# DownStream.net
KiCad netlist of a schematic drawn in Altium Designer
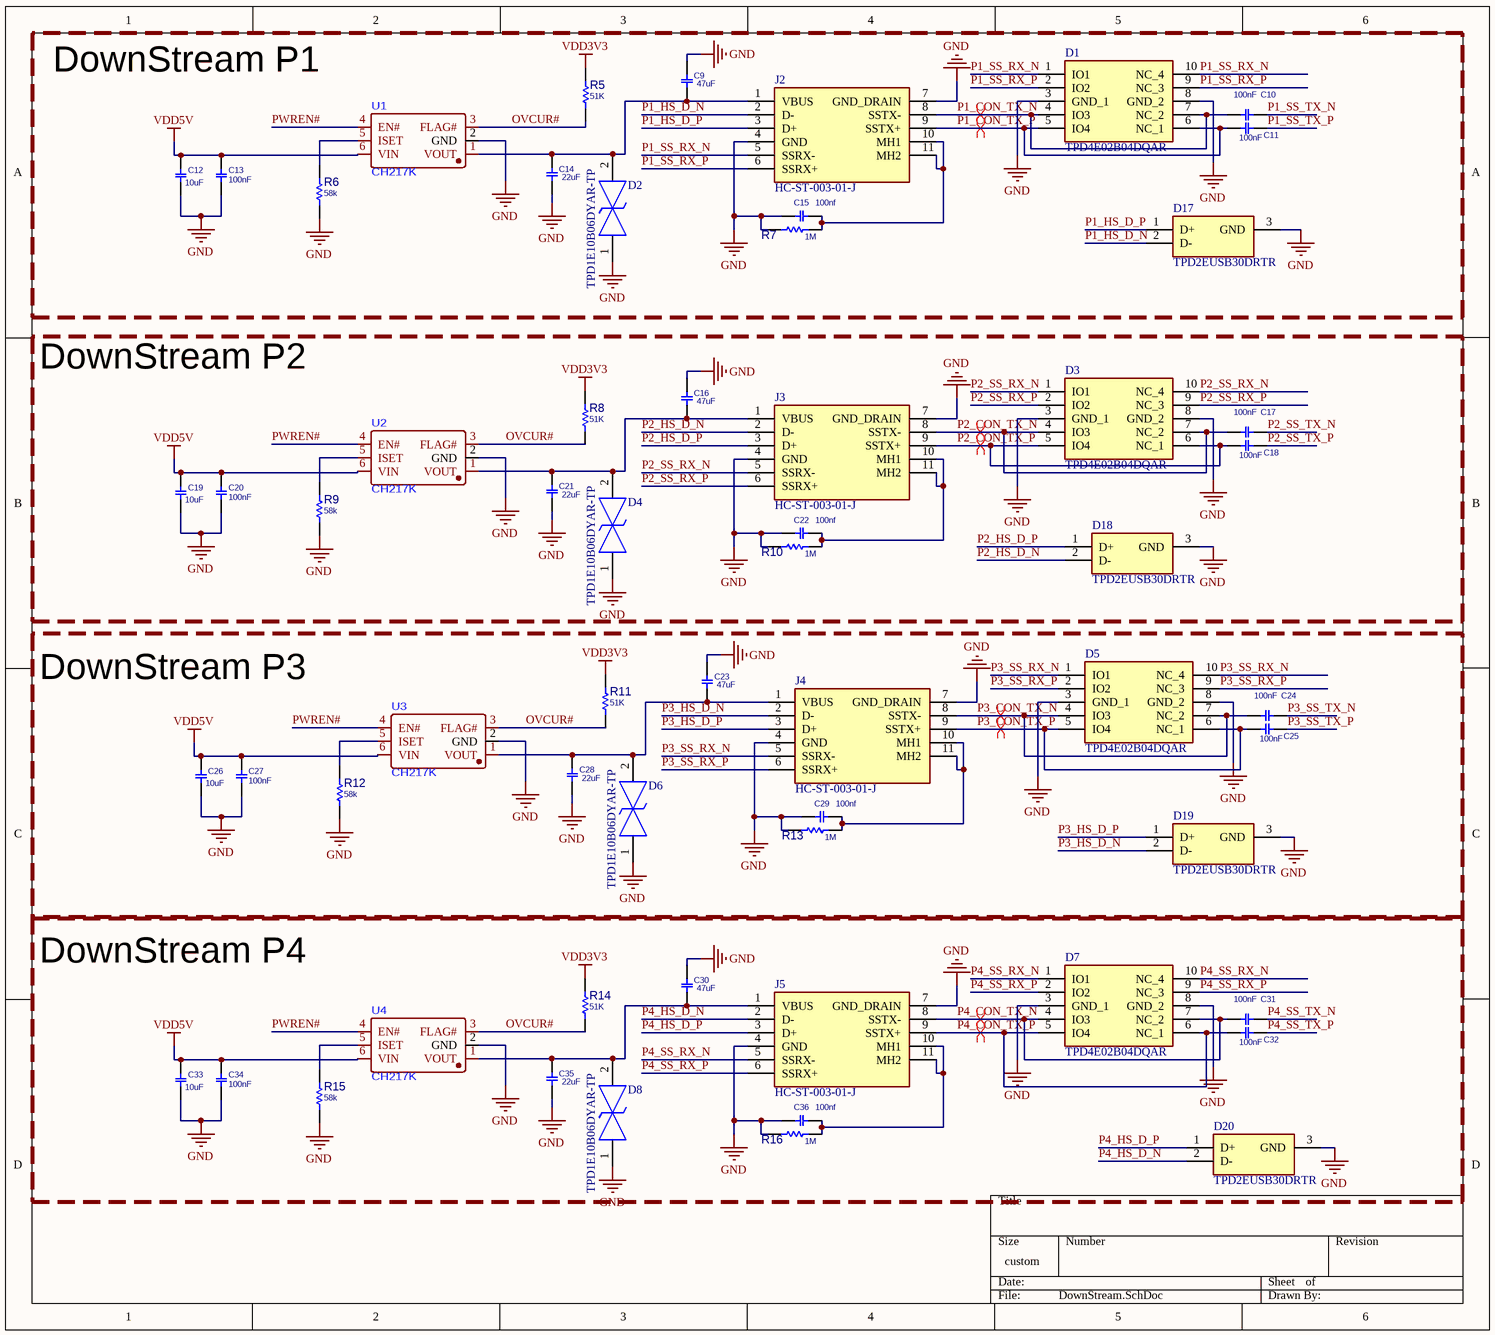
[diagram p0: DownStream.SchDoc]

(export (version "E")
  (design (tool "Eeschema 10.0.6"))
  (components
    (comp (ref "C9")
      (value "47uF")
      (footprint "C0805")
      (libsource (lib "passive_smd") (part "CAP_SMD_MLCC_0805"))
    )
    (comp (ref "C10")
      (value "100nF")
      (footprint "C0402")
      (libsource (lib "passive_smd") (part "CAP_SMD_MLCC_0402"))
    )
    (comp (ref "C11")
      (value "100nF")
      (footprint "C0402")
      (libsource (lib "passive_smd") (part "CAP_SMD_MLCC_0402"))
    )
    (comp (ref "C12")
      (value "10uF")
      (footprint "C0603")
      (description "CAP, MLCC, -F, -V, MATERIAL, -%, 0201")
      (libsource (lib "passive_smd") (part "CAP_SMD_MLCC_0603"))
    )
    (comp (ref "C13")
      (value "100nF")
      (footprint "C0402")
      (libsource (lib "passive_smd") (part "CAP_SMD_MLCC_0402"))
    )
    (comp (ref "C14")
      (value "22uF")
      (footprint "C0805")
      (libsource (lib "passive_smd") (part "CAP_SMD_MLCC_0805"))
    )
    (comp (ref "C15")
      (value "100nf")
      (footprint "C1812")
      (description "+1kv 100nf")
      (libsource (lib "passive_smd") (part "CAP_SMD_MLCC_1812"))
    )
    (comp (ref "C16")
      (value "47uF")
      (footprint "C0805")
      (libsource (lib "passive_smd") (part "CAP_SMD_MLCC_0805"))
    )
    (comp (ref "C17")
      (value "100nF")
      (footprint "C0402")
      (libsource (lib "passive_smd") (part "CAP_SMD_MLCC_0402"))
    )
    (comp (ref "C18")
      (value "100nF")
      (footprint "C0402")
      (libsource (lib "passive_smd") (part "CAP_SMD_MLCC_0402"))
    )
    (comp (ref "C19")
      (value "10uF")
      (footprint "C0603")
      (description "CAP, MLCC, -F, -V, MATERIAL, -%, 0201")
      (libsource (lib "passive_smd") (part "CAP_SMD_MLCC_0603"))
    )
    (comp (ref "C20")
      (value "100nF")
      (footprint "C0402")
      (libsource (lib "passive_smd") (part "CAP_SMD_MLCC_0402"))
    )
    (comp (ref "C21")
      (value "22uF")
      (footprint "C0805")
      (libsource (lib "passive_smd") (part "CAP_SMD_MLCC_0805"))
    )
    (comp (ref "C22")
      (value "100nf")
      (footprint "C1812")
      (description "+1kv 100nf")
      (libsource (lib "passive_smd") (part "CAP_SMD_MLCC_1812"))
    )
    (comp (ref "C23")
      (value "47uF")
      (footprint "C0805")
      (libsource (lib "passive_smd") (part "CAP_SMD_MLCC_0805"))
    )
    (comp (ref "C24")
      (value "100nF")
      (footprint "C0402")
      (libsource (lib "passive_smd") (part "CAP_SMD_MLCC_0402"))
    )
    (comp (ref "C25")
      (value "100nF")
      (footprint "C0402")
      (libsource (lib "passive_smd") (part "CAP_SMD_MLCC_0402"))
    )
    (comp (ref "C26")
      (value "10uF")
      (footprint "C0603")
      (libsource (lib "passive_smd") (part "CAP_SMD_MLCC_0603"))
    )
    (comp (ref "C27")
      (value "100nF")
      (footprint "C0402")
      (libsource (lib "passive_smd") (part "CAP_SMD_MLCC_0402"))
    )
    (comp (ref "C28")
      (value "22uF")
      (footprint "C0805")
      (libsource (lib "passive_smd") (part "CAP_SMD_MLCC_0805"))
    )
    (comp (ref "C29")
      (value "100nf")
      (footprint "C1812")
      (description "+1kv 100nf")
      (libsource (lib "passive_smd") (part "CAP_SMD_MLCC_1812"))
    )
    (comp (ref "C30")
      (value "47uF")
      (footprint "C0805")
      (libsource (lib "passive_smd") (part "CAP_SMD_MLCC_0805"))
    )
    (comp (ref "C31")
      (value "100nF")
      (footprint "C0402")
      (libsource (lib "passive_smd") (part "CAP_SMD_MLCC_0402"))
    )
    (comp (ref "C32")
      (value "100nF")
      (footprint "C0402")
      (libsource (lib "passive_smd") (part "CAP_SMD_MLCC_0402"))
    )
    (comp (ref "C33")
      (value "10uF")
      (footprint "C0603")
      (description "CAP, MLCC, -F, -V, MATERIAL, -%, 0201")
      (libsource (lib "passive_smd") (part "CAP_SMD_MLCC_0603"))
    )
    (comp (ref "C34")
      (value "100nF")
      (footprint "C0402")
      (libsource (lib "passive_smd") (part "CAP_SMD_MLCC_0402"))
    )
    (comp (ref "C35")
      (value "22uF")
      (footprint "C0805")
      (libsource (lib "passive_smd") (part "CAP_SMD_MLCC_0805"))
    )
    (comp (ref "C36")
      (value "100nf")
      (footprint "C1812")
      (description "+1kv 100nf")
      (libsource (lib "passive_smd") (part "CAP_SMD_MLCC_1812"))
    )
    (comp (ref "D1")
      (value "TPD4E02B04DQAR")
      (footprint "SamacSys:DQA(R-PUSON-N10)")
      (description "Diode")
      (fields (field (name "MOUSER PART NUMBER") "595-TPD4E02B04DQAR"))
      (libsource (lib "*") (part "TPD4E02B04DQAR"))
    )
    (comp (ref "D2")
      (value "TPD1E10B06DYAR-TP")
      (footprint "SamacSys:SODFL1608X77N")
      (description "TVS Diode (Bi-directional)")
      (fields
        (field (name "MANUFACTURER_PART_NUMBER") "TPD1E10B06DYARQ1")
        (field (name "MOUSER PART NUMBER") "595-TPD1E10B06DYARQ1")
      )
      (libsource (lib "*") (part "TPD1E10B06DYARQ1"))
    )
    (comp (ref "D3")
      (value "TPD4E02B04DQAR")
      (footprint "SamacSys:DQA(R-PUSON-N10)")
      (description "Diode")
      (fields (field (name "MOUSER PART NUMBER") "595-TPD4E02B04DQAR"))
      (libsource (lib "*") (part "TPD4E02B04DQAR"))
    )
    (comp (ref "D4")
      (value "TPD1E10B06DYAR-TP")
      (footprint "SamacSys:SODFL1608X77N")
      (description "TVS Diode (Bi-directional)")
      (fields
        (field (name "MANUFACTURER_PART_NUMBER") "TPD1E10B06DYARQ1")
        (field (name "MOUSER PART NUMBER") "595-TPD1E10B06DYARQ1")
      )
      (libsource (lib "*") (part "TPD1E10B06DYARQ1"))
    )
    (comp (ref "D5")
      (value "TPD4E02B04DQAR")
      (footprint "SamacSys:DQA(R-PUSON-N10)")
      (description "Diode")
      (fields (field (name "MOUSER PART NUMBER") "595-TPD4E02B04DQAR"))
      (libsource (lib "*") (part "TPD4E02B04DQAR"))
    )
    (comp (ref "D6")
      (value "TPD1E10B06DYAR-TP")
      (footprint "SamacSys:SODFL1608X77N")
      (description "TVS Diode (Bi-directional)")
      (fields
        (field (name "MANUFACTURER_PART_NUMBER") "TPD1E10B06DYARQ1")
        (field (name "MOUSER PART NUMBER") "595-TPD1E10B06DYARQ1")
      )
      (libsource (lib "*") (part "TPD1E10B06DYARQ1"))
    )
    (comp (ref "D7")
      (value "TPD4E02B04DQAR")
      (footprint "SamacSys:DQA(R-PUSON-N10)")
      (description "Diode")
      (fields (field (name "MOUSER PART NUMBER") "595-TPD4E02B04DQAR"))
      (libsource (lib "*") (part "TPD4E02B04DQAR"))
    )
    (comp (ref "D8")
      (value "TPD1E10B06DYAR-TP")
      (footprint "SamacSys:SODFL1608X77N")
      (description "TVS Diode (Bi-directional)")
      (fields
        (field (name "MANUFACTURER_PART_NUMBER") "TPD1E10B06DYARQ1")
        (field (name "MOUSER PART NUMBER") "595-TPD1E10B06DYARQ1")
      )
      (libsource (lib "*") (part "TPD1E10B06DYARQ1"))
    )
    (comp (ref "D17")
      (value "TPD2EUSB30DRTR")
      (footprint "SamacSys:SOTFL35P100X50-3N")
      (description "TPD2EUSB30ADRTR")
      (fields (field (name "MOUSER PART NUMBER") "595-TPD2EUSB30DRTR"))
      (libsource (lib "*") (part "TPD2EUSB30DRTR"))
    )
    (comp (ref "D18")
      (value "TPD2EUSB30DRTR")
      (footprint "SamacSys:SOTFL35P100X50-3N")
      (description "TPD2EUSB30ADRTR")
      (fields (field (name "MOUSER PART NUMBER") "595-TPD2EUSB30DRTR"))
      (libsource (lib "*") (part "TPD2EUSB30DRTR"))
    )
    (comp (ref "D19")
      (value "TPD2EUSB30DRTR")
      (footprint "SamacSys:SOTFL35P100X50-3N")
      (description "TPD2EUSB30ADRTR")
      (fields (field (name "MOUSER PART NUMBER") "595-TPD2EUSB30DRTR"))
      (libsource (lib "*") (part "TPD2EUSB30DRTR"))
    )
    (comp (ref "D20")
      (value "TPD2EUSB30DRTR")
      (footprint "SamacSys:SOTFL35P100X50-3N")
      (description "TPD2EUSB30ADRTR")
      (fields (field (name "MOUSER PART NUMBER") "595-TPD2EUSB30DRTR"))
      (libsource (lib "*") (part "TPD2EUSB30DRTR"))
    )
    (comp (ref "J2")
      (value "HC-ST-003-01-J")
      (footprint "SamacSys:GSB4111312HR")
      (description "Connector")
      (libsource (lib "*") (part "GSB4111312HR"))
    )
    (comp (ref "J3")
      (value "HC-ST-003-01-J")
      (footprint "SamacSys:GSB4111312HR")
      (description "Connector")
      (libsource (lib "*") (part "GSB4111312HR"))
    )
    (comp (ref "J4")
      (value "HC-ST-003-01-J")
      (footprint "SamacSys:GSB4111312HR")
      (description "Connector")
      (libsource (lib "*") (part "GSB4111312HR"))
    )
    (comp (ref "J5")
      (value "HC-ST-003-01-J")
      (footprint "SamacSys:GSB4111312HR")
      (description "Connector")
      (libsource (lib "*") (part "GSB4111312HR"))
    )
    (comp (ref "R5")
      (value "51K")
      (footprint "R0402")
      (description "RESISTOR, SMD")
      (libsource (lib "passive_smd") (part "RES_SMD_0402"))
    )
    (comp (ref "R6")
      (value "58k")
      (footprint "R0402")
      (description "RESISTOR, SMD")
      (libsource (lib "passive_smd") (part "RES_SMD_0402"))
    )
    (comp (ref "R7")
      (value "1M")
      (footprint "R0805")
      (description "RESISTOR, SMD")
      (libsource (lib "passive_smd") (part "RES_SMD_0402"))
    )
    (comp (ref "R8")
      (value "51K")
      (footprint "R0402")
      (description "RESISTOR, SMD")
      (libsource (lib "passive_smd") (part "RES_SMD_0402"))
    )
    (comp (ref "R9")
      (value "58k")
      (footprint "R0402")
      (description "RESISTOR, SMD")
      (libsource (lib "passive_smd") (part "RES_SMD_0402"))
    )
    (comp (ref "R10")
      (value "1M")
      (footprint "R0805")
      (description "RESISTOR, SMD")
      (libsource (lib "passive_smd") (part "RES_SMD_0402"))
    )
    (comp (ref "R11")
      (value "51K")
      (footprint "R0402")
      (description "RESISTOR, SMD")
      (libsource (lib "passive_smd") (part "RES_SMD_0402"))
    )
    (comp (ref "R12")
      (value "58k")
      (footprint "R0402")
      (description "RESISTOR, SMD")
      (libsource (lib "passive_smd") (part "RES_SMD_0402"))
    )
    (comp (ref "R13")
      (value "1M")
      (footprint "R0805")
      (description "RESISTOR, SMD")
      (libsource (lib "passive_smd") (part "RES_SMD_0402"))
    )
    (comp (ref "R14")
      (value "51K")
      (footprint "R0402")
      (description "RESISTOR, SMD")
      (libsource (lib "passive_smd") (part "RES_SMD_0402"))
    )
    (comp (ref "R15")
      (value "58k")
      (footprint "R0402")
      (description "RESISTOR, SMD")
      (libsource (lib "passive_smd") (part "RES_SMD_0402"))
    )
    (comp (ref "R16")
      (value "1M")
      (footprint "R0805")
      (description "RESISTOR, SMD")
      (libsource (lib "passive_smd") (part "RES_SMD_0402"))
    )
    (comp (ref "U1")
      (value "CH217K")
      (footprint "IC_IC-DP_SOT23-6L")
      (libsource (lib "Schlib1") (part "CH217K"))
    )
    (comp (ref "U2")
      (value "CH217K")
      (footprint "IC_IC-DP_SOT23-6L")
      (libsource (lib "Schlib1") (part "CH217K"))
    )
    (comp (ref "U3")
      (value "CH217K")
      (footprint "IC_IC-DP_SOT23-6L")
      (libsource (lib "Schlib1") (part "CH217K"))
    )
    (comp (ref "U4")
      (value "CH217K")
      (footprint "IC_IC-DP_SOT23-6L")
      (libsource (lib "Schlib1") (part "CH217K"))
    )
  )
  (nets
    (net (code "1") (name "/OVCUR#") (class "Default")
      (node (ref "R11") (pin "2") (pinfunction "2_2") (pintype "passive"))
      (node (ref "R14") (pin "2") (pinfunction "2_2") (pintype "passive"))
      (node (ref "R5") (pin "2") (pinfunction "2_2") (pintype "passive"))
      (node (ref "R8") (pin "2") (pinfunction "2_2") (pintype "passive"))
      (node (ref "U1") (pin "3") (pinfunction "FLAG#_3") (pintype "passive"))
      (node (ref "U2") (pin "3") (pinfunction "FLAG#_3") (pintype "passive"))
      (node (ref "U3") (pin "3") (pinfunction "FLAG#_3") (pintype "passive"))
      (node (ref "U4") (pin "3") (pinfunction "FLAG#_3") (pintype "passive"))
    )
    (net (code "2") (name "/P1_CON_TX_N") (class "Default")
      (node (ref "C10") (pin "2") (pinfunction "2_2") (pintype "passive"))
      (node (ref "D1") (pin "4") (pinfunction "IO3_4") (pintype "passive"))
      (node (ref "D1") (pin "7") (pinfunction "NC_2_7") (pintype "passive"))
      (node (ref "J2") (pin "8") (pinfunction "SSTX-_8") (pintype "passive"))
    )
    (net (code "3") (name "/P1_CON_TX_P") (class "Default")
      (node (ref "C11") (pin "2") (pinfunction "2_2") (pintype "passive"))
      (node (ref "D1") (pin "5") (pinfunction "IO4_5") (pintype "passive"))
      (node (ref "D1") (pin "6") (pinfunction "NC_1_6") (pintype "passive"))
      (node (ref "J2") (pin "9") (pinfunction "SSTX+_9") (pintype "passive"))
    )
    (net (code "4") (name "/P1_HS_D_N") (class "Default")
      (node (ref "D17") (pin "2") (pinfunction "D-_2") (pintype "passive"))
      (node (ref "J2") (pin "2") (pinfunction "D-_2") (pintype "passive"))
    )
    (net (code "5") (name "/P1_HS_D_P") (class "Default")
      (node (ref "D17") (pin "1") (pinfunction "D+_1") (pintype "passive"))
      (node (ref "J2") (pin "3") (pinfunction "D+_3") (pintype "passive"))
    )
    (net (code "6") (name "/P1_SS_RX_N") (class "Default")
      (node (ref "D1") (pin "1") (pinfunction "IO1_1") (pintype "passive"))
      (node (ref "D1") (pin "10") (pinfunction "NC_4_10") (pintype "passive"))
      (node (ref "J2") (pin "5") (pinfunction "SSRX-_5") (pintype "passive"))
    )
    (net (code "7") (name "/P1_SS_RX_P") (class "Default")
      (node (ref "D1") (pin "2") (pinfunction "IO2_2") (pintype "passive"))
      (node (ref "D1") (pin "9") (pinfunction "NC_3_9") (pintype "passive"))
      (node (ref "J2") (pin "6") (pinfunction "SSRX+_6") (pintype "passive"))
    )
    (net (code "8") (name "/P1_SS_TX_N") (class "Default")
      (node (ref "C10") (pin "1") (pinfunction "1_1") (pintype "passive"))
    )
    (net (code "9") (name "/P1_SS_TX_P") (class "Default")
      (node (ref "C11") (pin "1") (pinfunction "1_1") (pintype "passive"))
    )
    (net (code "10") (name "/P2_CON_TX_N") (class "Default")
      (node (ref "C17") (pin "2") (pinfunction "2_2") (pintype "passive"))
      (node (ref "D3") (pin "4") (pinfunction "IO3_4") (pintype "passive"))
      (node (ref "D3") (pin "7") (pinfunction "NC_2_7") (pintype "passive"))
      (node (ref "J3") (pin "8") (pinfunction "SSTX-_8") (pintype "passive"))
    )
    (net (code "11") (name "/P2_CON_TX_P") (class "Default")
      (node (ref "C18") (pin "2") (pinfunction "2_2") (pintype "passive"))
      (node (ref "D3") (pin "5") (pinfunction "IO4_5") (pintype "passive"))
      (node (ref "D3") (pin "6") (pinfunction "NC_1_6") (pintype "passive"))
      (node (ref "J3") (pin "9") (pinfunction "SSTX+_9") (pintype "passive"))
    )
    (net (code "12") (name "/P2_HS_D_N") (class "Default")
      (node (ref "D18") (pin "2") (pinfunction "D-_2") (pintype "passive"))
      (node (ref "J3") (pin "2") (pinfunction "D-_2") (pintype "passive"))
    )
    (net (code "13") (name "/P2_HS_D_P") (class "Default")
      (node (ref "D18") (pin "1") (pinfunction "D+_1") (pintype "passive"))
      (node (ref "J3") (pin "3") (pinfunction "D+_3") (pintype "passive"))
    )
    (net (code "14") (name "/P2_SS_RX_N") (class "Default")
      (node (ref "D3") (pin "1") (pinfunction "IO1_1") (pintype "passive"))
      (node (ref "D3") (pin "10") (pinfunction "NC_4_10") (pintype "passive"))
      (node (ref "J3") (pin "5") (pinfunction "SSRX-_5") (pintype "passive"))
    )
    (net (code "15") (name "/P2_SS_RX_P") (class "Default")
      (node (ref "D3") (pin "2") (pinfunction "IO2_2") (pintype "passive"))
      (node (ref "D3") (pin "9") (pinfunction "NC_3_9") (pintype "passive"))
      (node (ref "J3") (pin "6") (pinfunction "SSRX+_6") (pintype "passive"))
    )
    (net (code "16") (name "/P2_SS_TX_N") (class "Default")
      (node (ref "C17") (pin "1") (pinfunction "1_1") (pintype "passive"))
    )
    (net (code "17") (name "/P2_SS_TX_P") (class "Default")
      (node (ref "C18") (pin "1") (pinfunction "1_1") (pintype "passive"))
    )
    (net (code "18") (name "/P3_CON_TX_N") (class "Default")
      (node (ref "C24") (pin "2") (pinfunction "2_2") (pintype "passive"))
      (node (ref "D5") (pin "4") (pinfunction "IO3_4") (pintype "passive"))
      (node (ref "D5") (pin "7") (pinfunction "NC_2_7") (pintype "passive"))
      (node (ref "J4") (pin "8") (pinfunction "SSTX-_8") (pintype "passive"))
    )
    (net (code "19") (name "/P3_CON_TX_P") (class "Default")
      (node (ref "C25") (pin "2") (pinfunction "2_2") (pintype "passive"))
      (node (ref "D5") (pin "5") (pinfunction "IO4_5") (pintype "passive"))
      (node (ref "D5") (pin "6") (pinfunction "NC_1_6") (pintype "passive"))
      (node (ref "J4") (pin "9") (pinfunction "SSTX+_9") (pintype "passive"))
    )
    (net (code "20") (name "/P3_HS_D_N") (class "Default")
      (node (ref "D19") (pin "2") (pinfunction "D-_2") (pintype "passive"))
      (node (ref "J4") (pin "2") (pinfunction "D-_2") (pintype "passive"))
    )
    (net (code "21") (name "/P3_HS_D_P") (class "Default")
      (node (ref "D19") (pin "1") (pinfunction "D+_1") (pintype "passive"))
      (node (ref "J4") (pin "3") (pinfunction "D+_3") (pintype "passive"))
    )
    (net (code "22") (name "/P3_SS_RX_N") (class "Default")
      (node (ref "D5") (pin "1") (pinfunction "IO1_1") (pintype "passive"))
      (node (ref "D5") (pin "10") (pinfunction "NC_4_10") (pintype "passive"))
      (node (ref "J4") (pin "5") (pinfunction "SSRX-_5") (pintype "passive"))
    )
    (net (code "23") (name "/P3_SS_RX_P") (class "Default")
      (node (ref "D5") (pin "2") (pinfunction "IO2_2") (pintype "passive"))
      (node (ref "D5") (pin "9") (pinfunction "NC_3_9") (pintype "passive"))
      (node (ref "J4") (pin "6") (pinfunction "SSRX+_6") (pintype "passive"))
    )
    (net (code "24") (name "/P3_SS_TX_N") (class "Default")
      (node (ref "C24") (pin "1") (pinfunction "1_1") (pintype "passive"))
    )
    (net (code "25") (name "/P3_SS_TX_P") (class "Default")
      (node (ref "C25") (pin "1") (pinfunction "1_1") (pintype "passive"))
    )
    (net (code "26") (name "/P4_CON_TX_N") (class "Default")
      (node (ref "C31") (pin "2") (pinfunction "2_2") (pintype "passive"))
      (node (ref "D7") (pin "4") (pinfunction "IO3_4") (pintype "passive"))
      (node (ref "D7") (pin "7") (pinfunction "NC_2_7") (pintype "passive"))
      (node (ref "J5") (pin "8") (pinfunction "SSTX-_8") (pintype "passive"))
    )
    (net (code "27") (name "/P4_CON_TX_P") (class "Default")
      (node (ref "C32") (pin "2") (pinfunction "2_2") (pintype "passive"))
      (node (ref "D7") (pin "5") (pinfunction "IO4_5") (pintype "passive"))
      (node (ref "D7") (pin "6") (pinfunction "NC_1_6") (pintype "passive"))
      (node (ref "J5") (pin "9") (pinfunction "SSTX+_9") (pintype "passive"))
    )
    (net (code "28") (name "/P4_HS_D_N") (class "Default")
      (node (ref "D20") (pin "2") (pinfunction "D-_2") (pintype "passive"))
      (node (ref "J5") (pin "2") (pinfunction "D-_2") (pintype "passive"))
    )
    (net (code "29") (name "/P4_HS_D_P") (class "Default")
      (node (ref "D20") (pin "1") (pinfunction "D+_1") (pintype "passive"))
      (node (ref "J5") (pin "3") (pinfunction "D+_3") (pintype "passive"))
    )
    (net (code "30") (name "/P4_SS_RX_N") (class "Default")
      (node (ref "D7") (pin "1") (pinfunction "IO1_1") (pintype "passive"))
      (node (ref "D7") (pin "10") (pinfunction "NC_4_10") (pintype "passive"))
      (node (ref "J5") (pin "5") (pinfunction "SSRX-_5") (pintype "passive"))
    )
    (net (code "31") (name "/P4_SS_RX_P") (class "Default")
      (node (ref "D7") (pin "2") (pinfunction "IO2_2") (pintype "passive"))
      (node (ref "D7") (pin "9") (pinfunction "NC_3_9") (pintype "passive"))
      (node (ref "J5") (pin "6") (pinfunction "SSRX+_6") (pintype "passive"))
    )
    (net (code "32") (name "/P4_SS_TX_N") (class "Default")
      (node (ref "C31") (pin "1") (pinfunction "1_1") (pintype "passive"))
    )
    (net (code "33") (name "/P4_SS_TX_P") (class "Default")
      (node (ref "C32") (pin "1") (pinfunction "1_1") (pintype "passive"))
    )
    (net (code "34") (name "/PWREN#") (class "Default")
      (node (ref "U1") (pin "4") (pinfunction "EN#_4") (pintype "passive"))
      (node (ref "U2") (pin "4") (pinfunction "EN#_4") (pintype "passive"))
      (node (ref "U3") (pin "4") (pinfunction "EN#_4") (pintype "passive"))
      (node (ref "U4") (pin "4") (pinfunction "EN#_4") (pintype "passive"))
    )
    (net (code "35") (name "GND") (class "Default")
      (node (ref "C12") (pin "1") (pinfunction "1_1") (pintype "passive"))
      (node (ref "C13") (pin "2") (pinfunction "2_2") (pintype "passive"))
      (node (ref "C14") (pin "1") (pinfunction "1_1") (pintype "passive"))
      (node (ref "C15") (pin "1") (pinfunction "1_1") (pintype "passive"))
      (node (ref "C16") (pin "2") (pinfunction "2_2") (pintype "passive"))
      (node (ref "C19") (pin "1") (pinfunction "1_1") (pintype "passive"))
      (node (ref "C20") (pin "2") (pinfunction "2_2") (pintype "passive"))
      (node (ref "C21") (pin "1") (pinfunction "1_1") (pintype "passive"))
      (node (ref "C22") (pin "1") (pinfunction "1_1") (pintype "passive"))
      (node (ref "C23") (pin "2") (pinfunction "2_2") (pintype "passive"))
      (node (ref "C26") (pin "1") (pinfunction "1_1") (pintype "passive"))
      (node (ref "C27") (pin "2") (pinfunction "2_2") (pintype "passive"))
      (node (ref "C28") (pin "1") (pinfunction "1_1") (pintype "passive"))
      (node (ref "C29") (pin "1") (pinfunction "1_1") (pintype "passive"))
      (node (ref "C30") (pin "2") (pinfunction "2_2") (pintype "passive"))
      (node (ref "C33") (pin "1") (pinfunction "1_1") (pintype "passive"))
      (node (ref "C34") (pin "2") (pinfunction "2_2") (pintype "passive"))
      (node (ref "C35") (pin "1") (pinfunction "1_1") (pintype "passive"))
      (node (ref "C36") (pin "1") (pinfunction "1_1") (pintype "passive"))
      (node (ref "C9") (pin "2") (pinfunction "2_2") (pintype "passive"))
      (node (ref "D1") (pin "3") (pinfunction "GND_1_3") (pintype "passive"))
      (node (ref "D1") (pin "8") (pinfunction "GND_2_8") (pintype "passive"))
      (node (ref "D17") (pin "3") (pinfunction "GND_3") (pintype "passive"))
      (node (ref "D18") (pin "3") (pinfunction "GND_3") (pintype "passive"))
      (node (ref "D19") (pin "3") (pinfunction "GND_3") (pintype "passive"))
      (node (ref "D2") (pin "1") (pinfunction "1_1") (pintype "passive"))
      (node (ref "D20") (pin "3") (pinfunction "GND_3") (pintype "passive"))
      (node (ref "D3") (pin "3") (pinfunction "GND_1_3") (pintype "passive"))
      (node (ref "D3") (pin "8") (pinfunction "GND_2_8") (pintype "passive"))
      (node (ref "D4") (pin "1") (pinfunction "1_1") (pintype "passive"))
      (node (ref "D5") (pin "3") (pinfunction "GND_1_3") (pintype "passive"))
      (node (ref "D5") (pin "8") (pinfunction "GND_2_8") (pintype "passive"))
      (node (ref "D6") (pin "1") (pinfunction "1_1") (pintype "passive"))
      (node (ref "D7") (pin "3") (pinfunction "GND_1_3") (pintype "passive"))
      (node (ref "D7") (pin "8") (pinfunction "GND_2_8") (pintype "passive"))
      (node (ref "D8") (pin "1") (pinfunction "1_1") (pintype "passive"))
      (node (ref "J2") (pin "4") (pinfunction "GND_4") (pintype "passive"))
      (node (ref "J2") (pin "7") (pinfunction "GND_DRAIN_7") (pintype "passive"))
      (node (ref "J3") (pin "4") (pinfunction "GND_4") (pintype "passive"))
      (node (ref "J3") (pin "7") (pinfunction "GND_DRAIN_7") (pintype "passive"))
      (node (ref "J4") (pin "4") (pinfunction "GND_4") (pintype "passive"))
      (node (ref "J4") (pin "7") (pinfunction "GND_DRAIN_7") (pintype "passive"))
      (node (ref "J5") (pin "4") (pinfunction "GND_4") (pintype "passive"))
      (node (ref "J5") (pin "7") (pinfunction "GND_DRAIN_7") (pintype "passive"))
      (node (ref "R10") (pin "2") (pinfunction "2_2") (pintype "passive"))
      (node (ref "R12") (pin "2") (pinfunction "2_2") (pintype "passive"))
      (node (ref "R13") (pin "2") (pinfunction "2_2") (pintype "passive"))
      (node (ref "R15") (pin "2") (pinfunction "2_2") (pintype "passive"))
      (node (ref "R16") (pin "2") (pinfunction "2_2") (pintype "passive"))
      (node (ref "R6") (pin "2") (pinfunction "2_2") (pintype "passive"))
      (node (ref "R7") (pin "2") (pinfunction "2_2") (pintype "passive"))
      (node (ref "R9") (pin "2") (pinfunction "2_2") (pintype "passive"))
      (node (ref "U1") (pin "2") (pinfunction "GND_2") (pintype "passive"))
      (node (ref "U2") (pin "2") (pinfunction "GND_2") (pintype "passive"))
      (node (ref "U3") (pin "2") (pinfunction "GND_2") (pintype "passive"))
      (node (ref "U4") (pin "2") (pinfunction "GND_2") (pintype "passive"))
    )
    (net (code "36") (name "Net-(J2-MH1)") (class "Default")
      (node (ref "C15") (pin "2") (pinfunction "2_2") (pintype "passive"))
      (node (ref "J2") (pin "10") (pinfunction "MH1_10") (pintype "passive"))
      (node (ref "J2") (pin "11") (pinfunction "MH2_11") (pintype "passive"))
      (node (ref "R7") (pin "1") (pinfunction "1_1") (pintype "passive"))
    )
    (net (code "37") (name "Net-(J2-VBUS)") (class "Default")
      (node (ref "C14") (pin "2") (pinfunction "2_2") (pintype "passive"))
      (node (ref "C9") (pin "1") (pinfunction "1_1") (pintype "passive"))
      (node (ref "D2") (pin "2") (pinfunction "2_2") (pintype "passive"))
      (node (ref "J2") (pin "1") (pinfunction "VBUS_1") (pintype "passive"))
      (node (ref "U1") (pin "1") (pinfunction "VOUT_1") (pintype "passive"))
    )
    (net (code "38") (name "Net-(J3-MH1)") (class "Default")
      (node (ref "C22") (pin "2") (pinfunction "2_2") (pintype "passive"))
      (node (ref "J3") (pin "10") (pinfunction "MH1_10") (pintype "passive"))
      (node (ref "J3") (pin "11") (pinfunction "MH2_11") (pintype "passive"))
      (node (ref "R10") (pin "1") (pinfunction "1_1") (pintype "passive"))
    )
    (net (code "39") (name "Net-(J3-VBUS)") (class "Default")
      (node (ref "C16") (pin "1") (pinfunction "1_1") (pintype "passive"))
      (node (ref "C21") (pin "2") (pinfunction "2_2") (pintype "passive"))
      (node (ref "D4") (pin "2") (pinfunction "2_2") (pintype "passive"))
      (node (ref "J3") (pin "1") (pinfunction "VBUS_1") (pintype "passive"))
      (node (ref "U2") (pin "1") (pinfunction "VOUT_1") (pintype "passive"))
    )
    (net (code "40") (name "Net-(J4-MH1)") (class "Default")
      (node (ref "C29") (pin "2") (pinfunction "2_2") (pintype "passive"))
      (node (ref "J4") (pin "10") (pinfunction "MH1_10") (pintype "passive"))
      (node (ref "J4") (pin "11") (pinfunction "MH2_11") (pintype "passive"))
      (node (ref "R13") (pin "1") (pinfunction "1_1") (pintype "passive"))
    )
    (net (code "41") (name "Net-(J4-VBUS)") (class "Default")
      (node (ref "C23") (pin "1") (pinfunction "1_1") (pintype "passive"))
      (node (ref "C28") (pin "2") (pinfunction "2_2") (pintype "passive"))
      (node (ref "D6") (pin "2") (pinfunction "2_2") (pintype "passive"))
      (node (ref "J4") (pin "1") (pinfunction "VBUS_1") (pintype "passive"))
      (node (ref "U3") (pin "1") (pinfunction "VOUT_1") (pintype "passive"))
    )
    (net (code "42") (name "Net-(J5-MH1)") (class "Default")
      (node (ref "C36") (pin "2") (pinfunction "2_2") (pintype "passive"))
      (node (ref "J5") (pin "10") (pinfunction "MH1_10") (pintype "passive"))
      (node (ref "J5") (pin "11") (pinfunction "MH2_11") (pintype "passive"))
      (node (ref "R16") (pin "1") (pinfunction "1_1") (pintype "passive"))
    )
    (net (code "43") (name "Net-(J5-VBUS)") (class "Default")
      (node (ref "C30") (pin "1") (pinfunction "1_1") (pintype "passive"))
      (node (ref "C35") (pin "2") (pinfunction "2_2") (pintype "passive"))
      (node (ref "D8") (pin "2") (pinfunction "2_2") (pintype "passive"))
      (node (ref "J5") (pin "1") (pinfunction "VBUS_1") (pintype "passive"))
      (node (ref "U4") (pin "1") (pinfunction "VOUT_1") (pintype "passive"))
    )
    (net (code "44") (name "Net-(U1-ISET)") (class "Default")
      (node (ref "R6") (pin "1") (pinfunction "1_1") (pintype "passive"))
      (node (ref "U1") (pin "5") (pinfunction "ISET_5") (pintype "passive"))
    )
    (net (code "45") (name "Net-(U2-ISET)") (class "Default")
      (node (ref "R9") (pin "1") (pinfunction "1_1") (pintype "passive"))
      (node (ref "U2") (pin "5") (pinfunction "ISET_5") (pintype "passive"))
    )
    (net (code "46") (name "Net-(U3-ISET)") (class "Default")
      (node (ref "R12") (pin "1") (pinfunction "1_1") (pintype "passive"))
      (node (ref "U3") (pin "5") (pinfunction "ISET_5") (pintype "passive"))
    )
    (net (code "47") (name "Net-(U4-ISET)") (class "Default")
      (node (ref "R15") (pin "1") (pinfunction "1_1") (pintype "passive"))
      (node (ref "U4") (pin "5") (pinfunction "ISET_5") (pintype "passive"))
    )
    (net (code "48") (name "VDD3V3") (class "Default")
      (node (ref "R11") (pin "1") (pinfunction "1_1") (pintype "passive"))
      (node (ref "R14") (pin "1") (pinfunction "1_1") (pintype "passive"))
      (node (ref "R5") (pin "1") (pinfunction "1_1") (pintype "passive"))
      (node (ref "R8") (pin "1") (pinfunction "1_1") (pintype "passive"))
    )
    (net (code "49") (name "VDD5V") (class "Default")
      (node (ref "C12") (pin "2") (pinfunction "2_2") (pintype "passive"))
      (node (ref "C13") (pin "1") (pinfunction "1_1") (pintype "passive"))
      (node (ref "C19") (pin "2") (pinfunction "2_2") (pintype "passive"))
      (node (ref "C20") (pin "1") (pinfunction "1_1") (pintype "passive"))
      (node (ref "C26") (pin "2") (pinfunction "2_2") (pintype "passive"))
      (node (ref "C27") (pin "1") (pinfunction "1_1") (pintype "passive"))
      (node (ref "C33") (pin "2") (pinfunction "2_2") (pintype "passive"))
      (node (ref "C34") (pin "1") (pinfunction "1_1") (pintype "passive"))
      (node (ref "U1") (pin "6") (pinfunction "VIN_6") (pintype "passive"))
      (node (ref "U2") (pin "6") (pinfunction "VIN_6") (pintype "passive"))
      (node (ref "U3") (pin "6") (pinfunction "VIN_6") (pintype "passive"))
      (node (ref "U4") (pin "6") (pinfunction "VIN_6") (pintype "passive"))
    )
  )
)
